# Main.net
KiCad netlist of a schematic drawn in Altium Designer
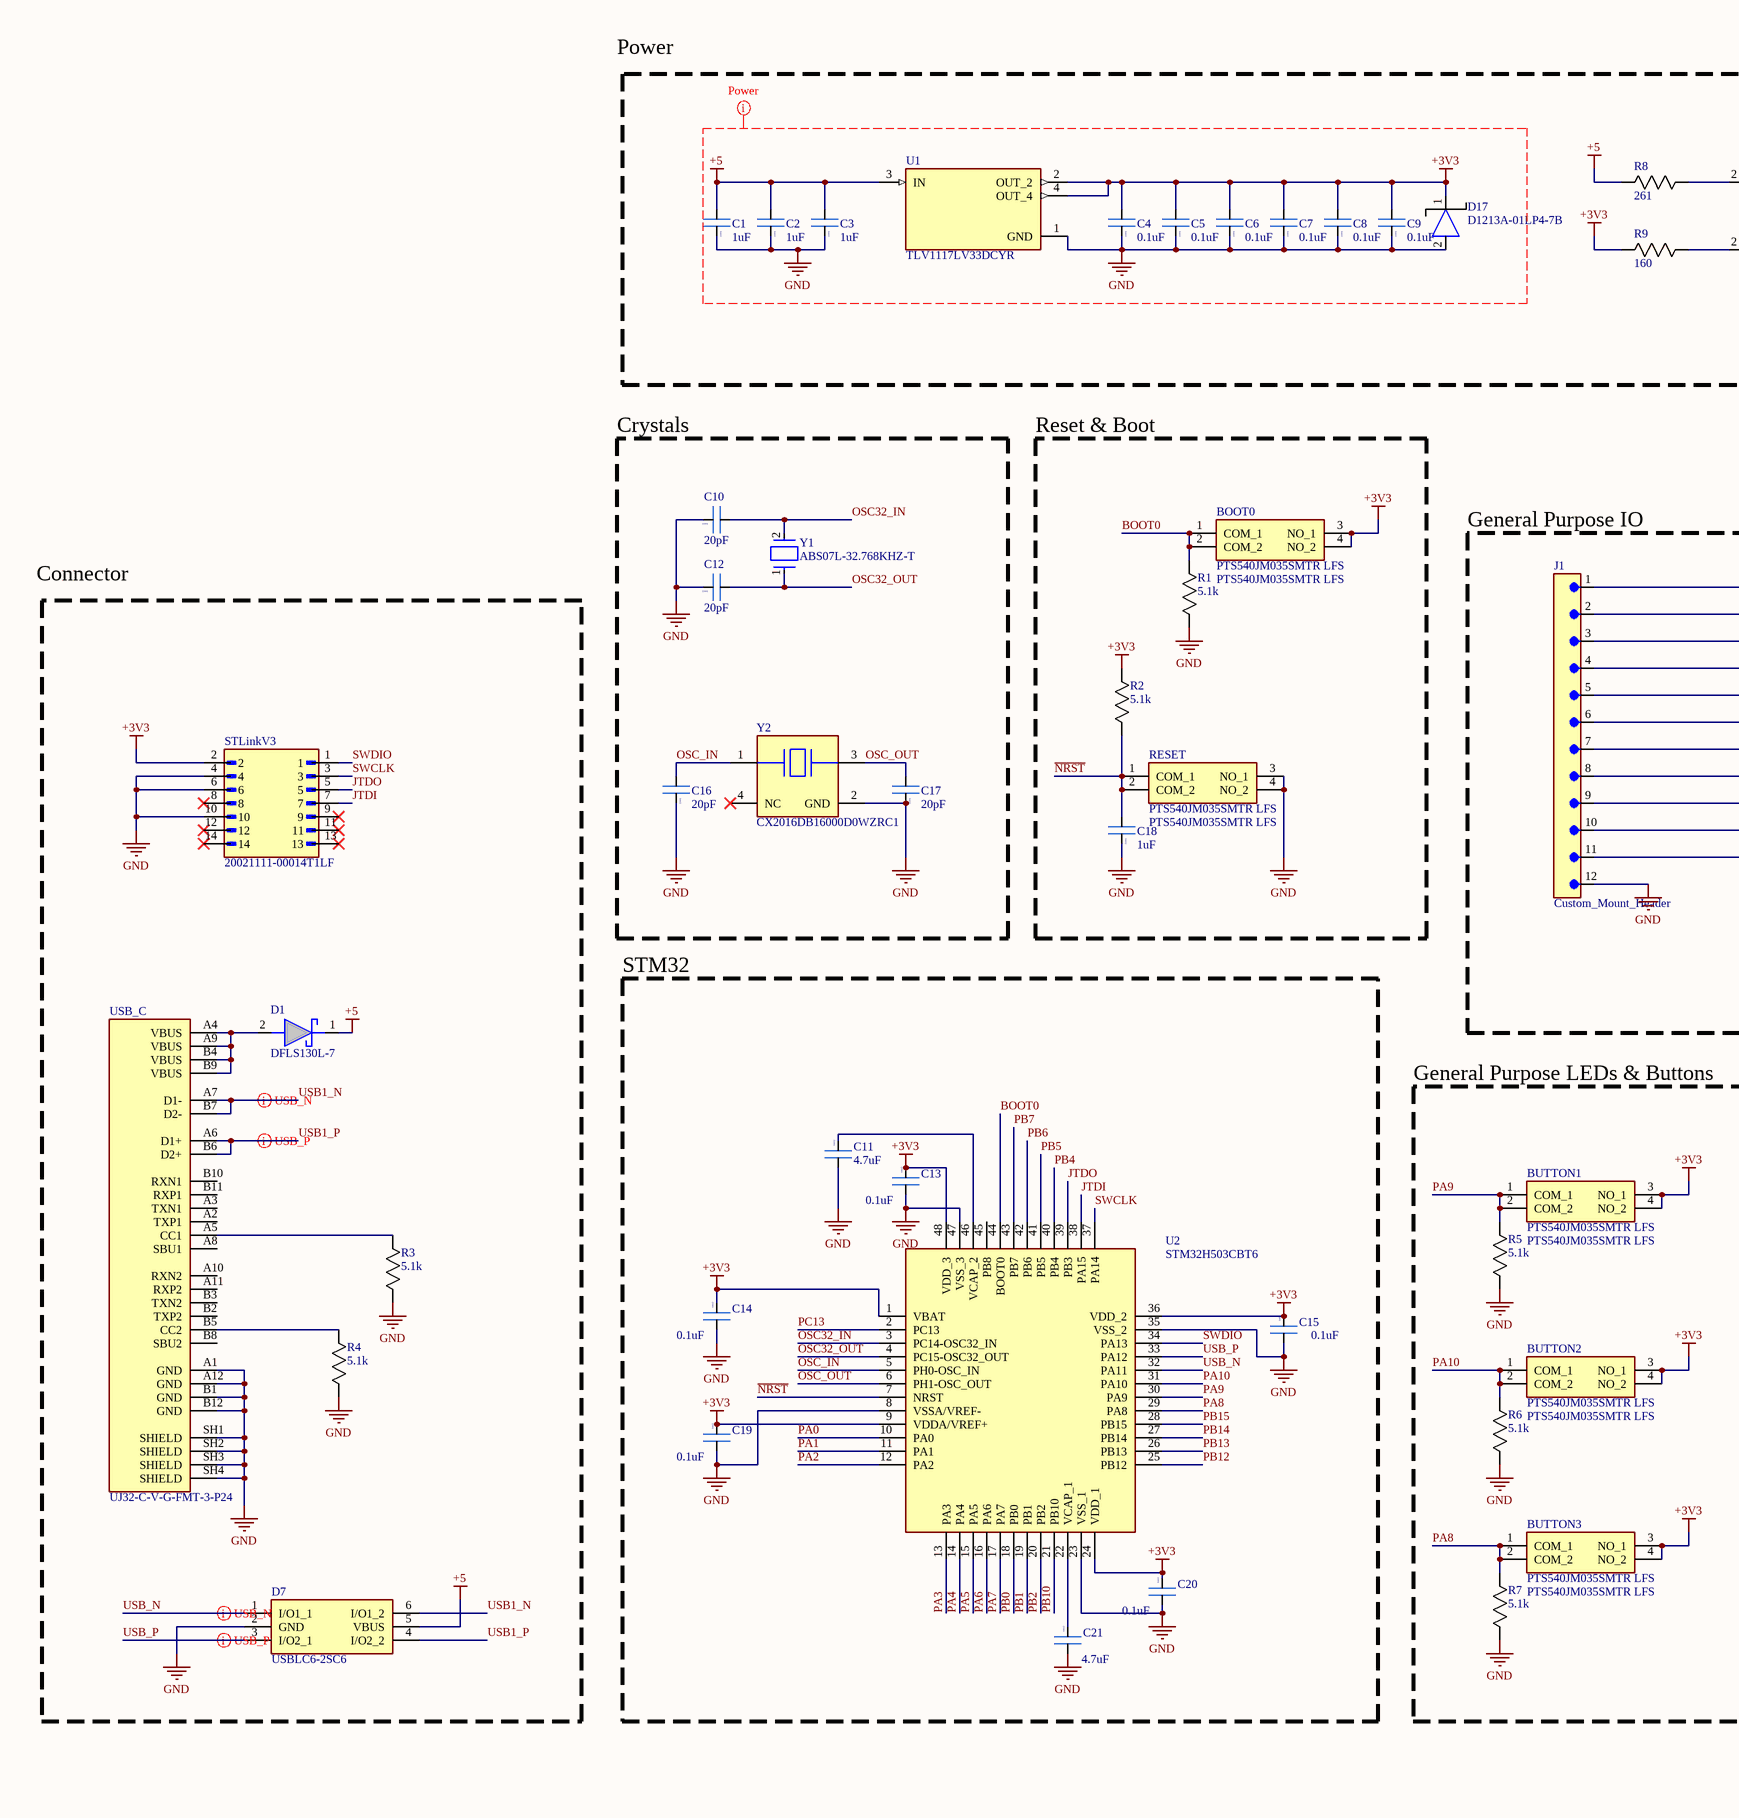
[diagram p0: Main.SchDoc, left]
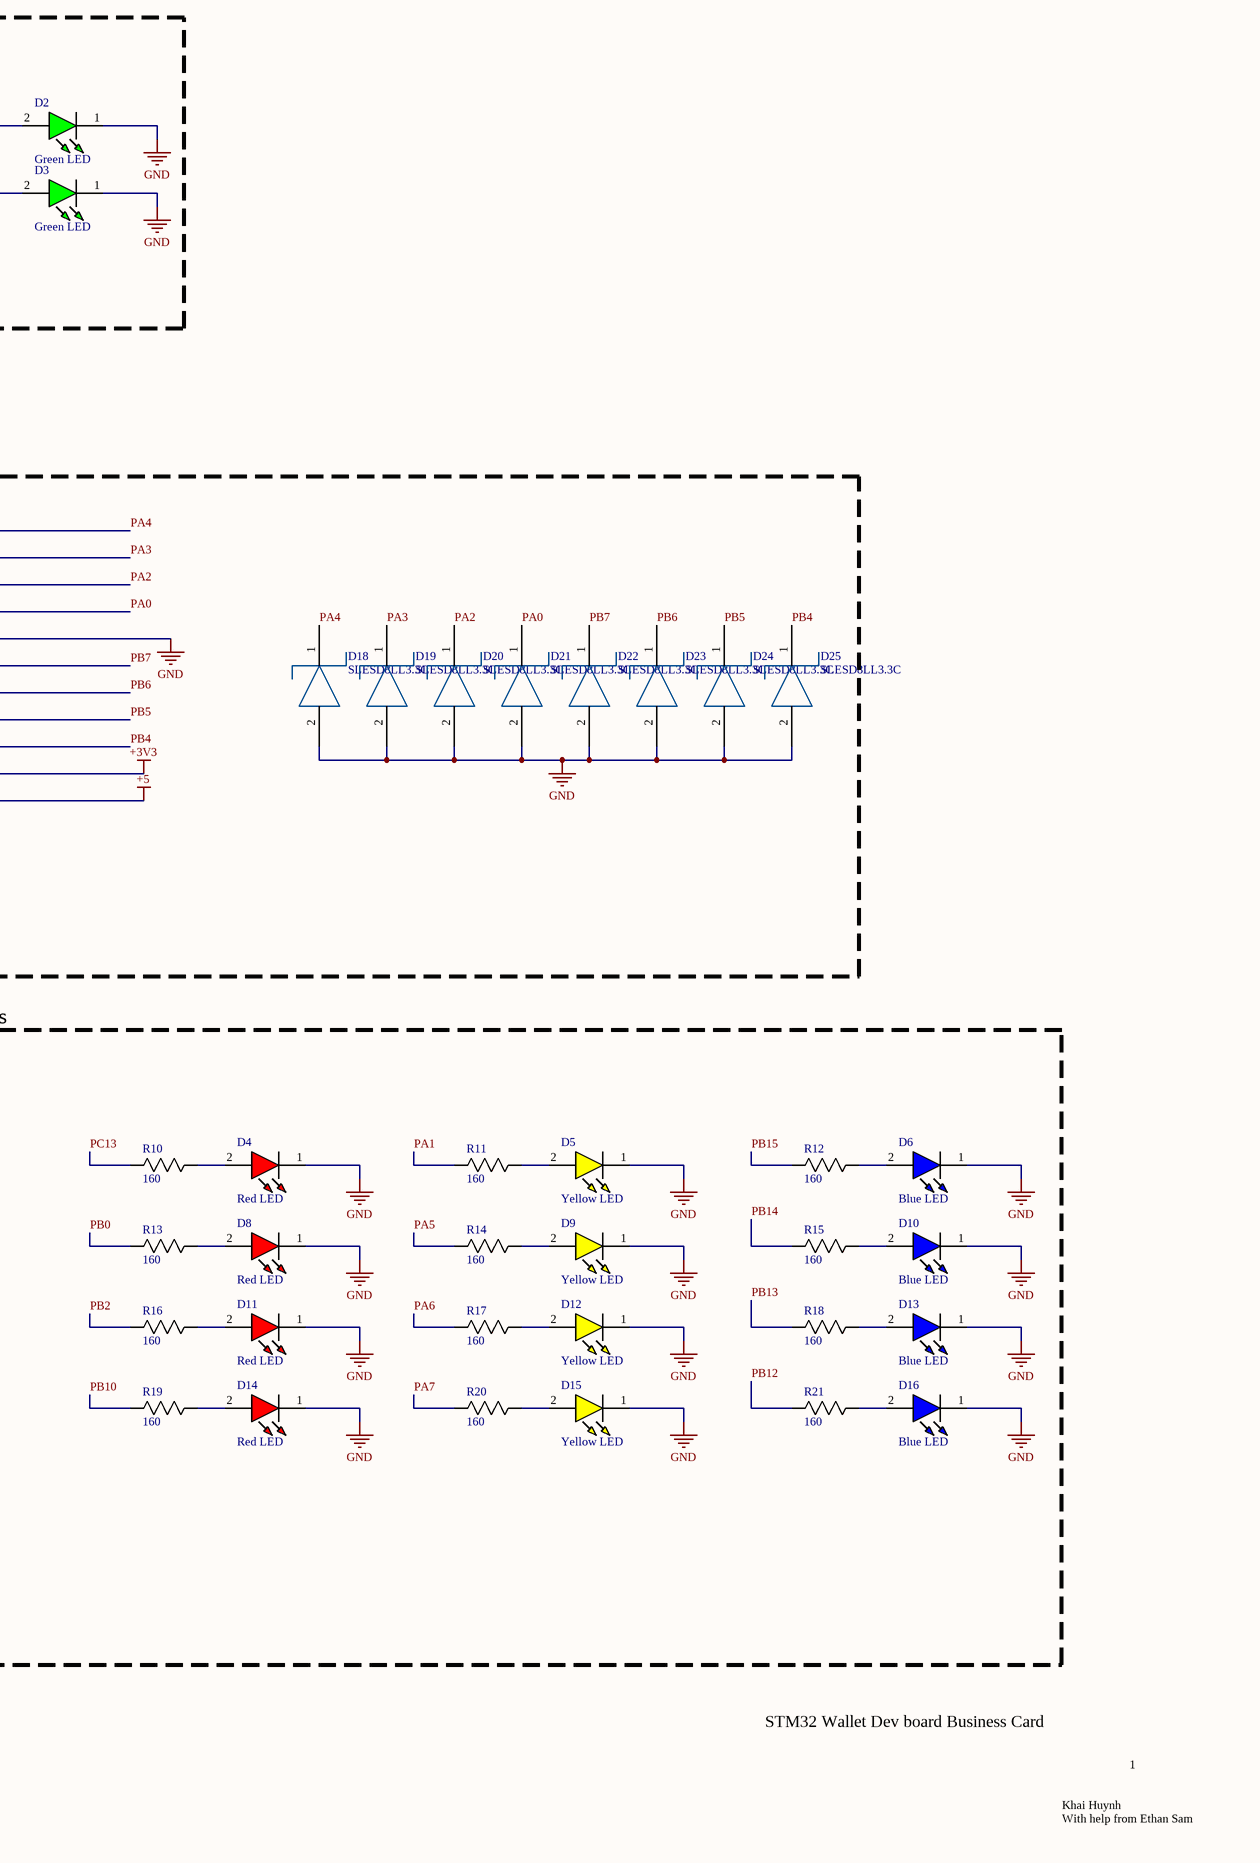
[diagram p1: Main.SchDoc, right]

(export (version "E")
  (design (tool "Eeschema 10.0.6"))
  (components
    (comp (ref "BOOT0")
      (value "PTS540JM035SMTR LFS")
      (footprint "PTS540JM035SMTR LFS")
      (libsource (lib "Schlib1") (part "PTS540JM035SMTR LFS"))
    )
    (comp (ref "BUTTON1")
      (value "PTS540JM035SMTR LFS")
      (footprint "PTS540JM035SMTR LFS")
      (libsource (lib "Schlib1") (part "PTS540JM035SMTR LFS"))
    )
    (comp (ref "BUTTON2")
      (value "PTS540JM035SMTR LFS")
      (footprint "PTS540JM035SMTR LFS")
      (libsource (lib "Schlib1") (part "PTS540JM035SMTR LFS"))
    )
    (comp (ref "BUTTON3")
      (value "PTS540JM035SMTR LFS")
      (footprint "PTS540JM035SMTR LFS")
      (libsource (lib "Schlib1") (part "PTS540JM035SMTR LFS"))
    )
    (comp (ref "C1")
      (value "1uF")
      (footprint "0402 Capacitor")
      (libsource (lib "Schlib1") (part "0402 Capacitor"))
    )
    (comp (ref "C2")
      (value "1uF")
      (footprint "0402 Capacitor")
      (libsource (lib "Schlib1") (part "0402 Capacitor"))
    )
    (comp (ref "C3")
      (value "1uF")
      (footprint "0402 Capacitor")
      (libsource (lib "Schlib1") (part "0402 Capacitor"))
    )
    (comp (ref "C4")
      (value "0.1uF")
      (footprint "0402 Capacitor")
      (libsource (lib "Schlib1") (part "0402 Capacitor"))
    )
    (comp (ref "C5")
      (value "0.1uF")
      (footprint "0402 Capacitor")
      (libsource (lib "Schlib1") (part "0402 Capacitor"))
    )
    (comp (ref "C6")
      (value "0.1uF")
      (footprint "0402 Capacitor")
      (libsource (lib "Schlib1") (part "0402 Capacitor"))
    )
    (comp (ref "C7")
      (value "0.1uF")
      (footprint "0402 Capacitor")
      (libsource (lib "Schlib1") (part "0402 Capacitor"))
    )
    (comp (ref "C8")
      (value "0.1uF")
      (footprint "0402 Capacitor")
      (libsource (lib "Schlib1") (part "0402 Capacitor"))
    )
    (comp (ref "C9")
      (value "0.1uF")
      (footprint "0402 Capacitor")
      (libsource (lib "Schlib1") (part "0402 Capacitor"))
    )
    (comp (ref "C10")
      (value "20pF")
      (footprint "0402 Capacitor")
      (libsource (lib "Schlib1") (part "0402 Capacitor"))
    )
    (comp (ref "C11")
      (value "4.7uF")
      (footprint "0402 Capacitor")
      (libsource (lib "Schlib1") (part "0402 Capacitor"))
    )
    (comp (ref "C12")
      (value "20pF")
      (footprint "0402 Capacitor")
      (libsource (lib "Schlib1") (part "0402 Capacitor"))
    )
    (comp (ref "C13")
      (value "0.1uF")
      (footprint "0402 Capacitor")
      (libsource (lib "Schlib1") (part "0402 Capacitor"))
    )
    (comp (ref "C14")
      (value "0.1uF")
      (footprint "0402 Capacitor")
      (libsource (lib "Schlib1") (part "0402 Capacitor"))
    )
    (comp (ref "C15")
      (value "0.1uF")
      (footprint "0402 Capacitor")
      (libsource (lib "Schlib1") (part "0402 Capacitor"))
    )
    (comp (ref "C16")
      (value "20pF")
      (footprint "0402 Capacitor")
      (libsource (lib "Schlib1") (part "0402 Capacitor"))
    )
    (comp (ref "C17")
      (value "20pF")
      (footprint "0402 Capacitor")
      (libsource (lib "Schlib1") (part "0402 Capacitor"))
    )
    (comp (ref "C18")
      (value "1uF")
      (footprint "0402 Capacitor")
      (libsource (lib "Schlib1") (part "0402 Capacitor"))
    )
    (comp (ref "C19")
      (value "0.1uF")
      (footprint "0402 Capacitor")
      (libsource (lib "Schlib1") (part "0402 Capacitor"))
    )
    (comp (ref "C20")
      (value "0.1uF")
      (footprint "0402 Capacitor")
      (libsource (lib "Schlib1") (part "0402 Capacitor"))
    )
    (comp (ref "C21")
      (value "4.7uF")
      (footprint "0402 Capacitor")
      (libsource (lib "Schlib1") (part "0402 Capacitor"))
    )
    (comp (ref "D1")
      (value "DFLS130L-7")
      (footprint "PCBComponent_1")
      (libsource (lib "Schlib1") (part "DFLS130L-7"))
    )
    (comp (ref "D2")
      (value "Green LED")
      (footprint "0603 LED")
      (description "APG1608CGKC/T")
      (libsource (lib "Schlib1") (part "Green LED"))
    )
    (comp (ref "D3")
      (value "Green LED")
      (footprint "0603 LED")
      (description "APG1608CGKC/T")
      (libsource (lib "Schlib1") (part "Green LED"))
    )
    (comp (ref "D4")
      (value "Red LED")
      (footprint "0603 LED")
      (description "APG1608SURKC/T")
      (libsource (lib "Schlib1") (part "Red LED"))
    )
    (comp (ref "D5")
      (value "Yellow LED")
      (footprint "0603 LED")
      (description "APG1608SYKC/T")
      (libsource (lib "Schlib1") (part "White LED"))
    )
    (comp (ref "D6")
      (value "Blue LED")
      (footprint "0603 LED")
      (description "APG1608QBC/D")
      (libsource (lib "Schlib1") (part "Blue LED"))
    )
    (comp (ref "D7")
      (value "USBLC6-2SC6")
      (footprint "USBLC6-2SC6")
      (libsource (lib "Schlib1") (part "USBLC6-2SC6"))
    )
    (comp (ref "D8")
      (value "Red LED")
      (footprint "0603 LED")
      (description "APG1608SURKC/T")
      (libsource (lib "Schlib1") (part "Red LED"))
    )
    (comp (ref "D9")
      (value "Yellow LED")
      (footprint "0603 LED")
      (description "APG1608SYKC/T")
      (libsource (lib "Schlib1") (part "White LED"))
    )
    (comp (ref "D10")
      (value "Blue LED")
      (footprint "0603 LED")
      (description "APG1608QBC/D")
      (libsource (lib "Schlib1") (part "Blue LED"))
    )
    (comp (ref "D11")
      (value "Red LED")
      (footprint "0603 LED")
      (description "APG1608SURKC/T")
      (libsource (lib "Schlib1") (part "Red LED"))
    )
    (comp (ref "D12")
      (value "Yellow LED")
      (footprint "0603 LED")
      (description "APG1608SYKC/T")
      (libsource (lib "Schlib1") (part "White LED"))
    )
    (comp (ref "D13")
      (value "Blue LED")
      (footprint "0603 LED")
      (description "APG1608QBC/D")
      (libsource (lib "Schlib1") (part "Blue LED"))
    )
    (comp (ref "D14")
      (value "Red LED")
      (footprint "0603 LED")
      (description "APG1608SURKC/T")
      (libsource (lib "Schlib1") (part "Red LED"))
    )
    (comp (ref "D15")
      (value "Yellow LED")
      (footprint "0603 LED")
      (description "APG1608SYKC/T")
      (libsource (lib "Schlib1") (part "White LED"))
    )
    (comp (ref "D16")
      (value "Blue LED")
      (footprint "0603 LED")
      (description "APG1608QBC/D")
      (libsource (lib "Schlib1") (part "Blue LED"))
    )
    (comp (ref "D17")
      (value "D1213A-01LP4-7B")
      (footprint "SLESD8LL3.3C")
      (libsource (lib "Schlib1") (part "D1213A-01LP4-7B"))
    )
    (comp (ref "D18")
      (value "SLESD8LL3.3C")
      (footprint "SLESD8LL3.3C")
      (libsource (lib "Schlib1") (part "SLESD8LL3.3C"))
    )
    (comp (ref "D19")
      (value "SLESD8LL3.3C")
      (footprint "SLESD8LL3.3C")
      (libsource (lib "Schlib1") (part "SLESD8LL3.3C"))
    )
    (comp (ref "D20")
      (value "SLESD8LL3.3C")
      (footprint "SLESD8LL3.3C")
      (libsource (lib "Schlib1") (part "SLESD8LL3.3C"))
    )
    (comp (ref "D21")
      (value "SLESD8LL3.3C")
      (footprint "SLESD8LL3.3C")
      (libsource (lib "Schlib1") (part "SLESD8LL3.3C"))
    )
    (comp (ref "D22")
      (value "SLESD8LL3.3C")
      (footprint "SLESD8LL3.3C")
      (libsource (lib "Schlib1") (part "SLESD8LL3.3C"))
    )
    (comp (ref "D23")
      (value "SLESD8LL3.3C")
      (footprint "SLESD8LL3.3C")
      (libsource (lib "Schlib1") (part "SLESD8LL3.3C"))
    )
    (comp (ref "D24")
      (value "SLESD8LL3.3C")
      (footprint "SLESD8LL3.3C")
      (libsource (lib "Schlib1") (part "SLESD8LL3.3C"))
    )
    (comp (ref "D25")
      (value "SLESD8LL3.3C")
      (footprint "SLESD8LL3.3C")
      (libsource (lib "Schlib1") (part "SLESD8LL3.3C"))
    )
    (comp (ref "J1")
      (value "Custom_Mount_Header")
      (footprint "Custom_header")
      (libsource (lib "Schlib1") (part "Custom_Mount_Header"))
    )
    (comp (ref "R1")
      (value "5.1k")
      (footprint "0402 Resistor")
      (libsource (lib "Schlib1") (part "0402 Resistor"))
    )
    (comp (ref "R2")
      (value "5.1k")
      (footprint "0402 Resistor")
      (libsource (lib "Schlib1") (part "0402 Resistor"))
    )
    (comp (ref "R3")
      (value "5.1k")
      (footprint "0402 Resistor")
      (libsource (lib "Schlib1") (part "0402 Resistor"))
    )
    (comp (ref "R4")
      (value "5.1k")
      (footprint "0402 Resistor")
      (libsource (lib "Schlib1") (part "0402 Resistor"))
    )
    (comp (ref "R5")
      (value "5.1k")
      (footprint "0402 Resistor")
      (libsource (lib "Schlib1") (part "0402 Resistor"))
    )
    (comp (ref "R6")
      (value "5.1k")
      (footprint "0402 Resistor")
      (libsource (lib "Schlib1") (part "0402 Resistor"))
    )
    (comp (ref "R7")
      (value "5.1k")
      (footprint "0402 Resistor")
      (libsource (lib "Schlib1") (part "0402 Resistor"))
    )
    (comp (ref "R8")
      (value "261")
      (footprint "0402 Resistor")
      (libsource (lib "Schlib1") (part "0402 Resistor"))
    )
    (comp (ref "R9")
      (value "160")
      (footprint "0402 Resistor")
      (libsource (lib "Schlib1") (part "0402 Resistor"))
    )
    (comp (ref "R10")
      (value "160")
      (footprint "0402 Resistor")
      (libsource (lib "Schlib1") (part "0402 Resistor"))
    )
    (comp (ref "R11")
      (value "160")
      (footprint "0402 Resistor")
      (libsource (lib "Schlib1") (part "0402 Resistor"))
    )
    (comp (ref "R12")
      (value "160")
      (footprint "0402 Resistor")
      (libsource (lib "Schlib1") (part "0402 Resistor"))
    )
    (comp (ref "R13")
      (value "160")
      (footprint "0402 Resistor")
      (libsource (lib "Schlib1") (part "0402 Resistor"))
    )
    (comp (ref "R14")
      (value "160")
      (footprint "0402 Resistor")
      (libsource (lib "Schlib1") (part "0402 Resistor"))
    )
    (comp (ref "R15")
      (value "160")
      (footprint "0402 Resistor")
      (libsource (lib "Schlib1") (part "0402 Resistor"))
    )
    (comp (ref "R16")
      (value "160")
      (footprint "0402 Resistor")
      (libsource (lib "Schlib1") (part "0402 Resistor"))
    )
    (comp (ref "R17")
      (value "160")
      (footprint "0402 Resistor")
      (libsource (lib "Schlib1") (part "0402 Resistor"))
    )
    (comp (ref "R18")
      (value "160")
      (footprint "0402 Resistor")
      (libsource (lib "Schlib1") (part "0402 Resistor"))
    )
    (comp (ref "R19")
      (value "160")
      (footprint "0402 Resistor")
      (libsource (lib "Schlib1") (part "0402 Resistor"))
    )
    (comp (ref "R20")
      (value "160")
      (footprint "0402 Resistor")
      (libsource (lib "Schlib1") (part "0402 Resistor"))
    )
    (comp (ref "R21")
      (value "160")
      (footprint "0402 Resistor")
      (libsource (lib "Schlib1") (part "0402 Resistor"))
    )
    (comp (ref "RESET")
      (value "PTS540JM035SMTR LFS")
      (footprint "PTS540JM035SMTR LFS")
      (libsource (lib "Schlib1") (part "PTS540JM035SMTR LFS"))
    )
    (comp (ref "STLinkV3")
      (value "20021111-00014T1LF")
      (footprint "20021111-00014T1LF")
      (libsource (lib "Schlib1") (part "20021111-00014T1LF"))
    )
    (comp (ref "U1")
      (value "TLV1117LV33DCYR")
      (footprint "TLV1117LV33DCYR")
      (libsource (lib "Schlib1") (part "TLV1117LV33DCYR"))
    )
    (comp (ref "U2")
      (value "STM32H503CBT6")
      (footprint "STM32H503")
      (libsource (lib "Schlib1") (part "STM32H503CBT6"))
    )
    (comp (ref "USB_C")
      (value "UJ32-C-V-G-FMT-3-P24")
      (footprint "UJ32-C-V-G-FMT-3-P24")
      (libsource (lib "Schlib1") (part "UJ32-C-V-G-FMT-3-P24"))
    )
    (comp (ref "Y1")
      (value "ABS07L-32.768KHZ-T")
      (footprint "FP-ABS07L-MFG")
      (description "CRYSTAL 32.7680KHZ 12.5PF SMD")
      (fields (field (name "TOLERANCE") "20ppm"))
      (libsource (lib "Altium Content Vault") (part "c23a69dc6c9e2f18f2079038eb95dd1"))
    )
    (comp (ref "Y2")
      (value "CX2016DB16000D0WZRC1")
      (footprint "CX2016DB16000D0WZRC1")
      (libsource (lib "Schlib1") (part "CX2016DB16000D0WZRC1"))
    )
  )
  (nets
    (net (code "1") (name "+3V3") (class "Default")
      (node (ref "BOOT0") (pin "3") (pinfunction "NO_1_3") (pintype "passive"))
      (node (ref "BOOT0") (pin "4") (pinfunction "NO_2_4") (pintype "passive"))
      (node (ref "BUTTON1") (pin "3") (pinfunction "NO_1_3") (pintype "passive"))
      (node (ref "BUTTON1") (pin "4") (pinfunction "NO_2_4") (pintype "passive"))
      (node (ref "BUTTON2") (pin "3") (pinfunction "NO_1_3") (pintype "passive"))
      (node (ref "BUTTON2") (pin "4") (pinfunction "NO_2_4") (pintype "passive"))
      (node (ref "BUTTON3") (pin "3") (pinfunction "NO_1_3") (pintype "passive"))
      (node (ref "BUTTON3") (pin "4") (pinfunction "NO_2_4") (pintype "passive"))
      (node (ref "C13") (pin "1") (pinfunction "1_1") (pintype "passive"))
      (node (ref "C14") (pin "1") (pinfunction "1_1") (pintype "passive"))
      (node (ref "C15") (pin "1") (pinfunction "1_1") (pintype "passive"))
      (node (ref "C19") (pin "1") (pinfunction "1_1") (pintype "passive"))
      (node (ref "C20") (pin "1") (pinfunction "1_1") (pintype "passive"))
      (node (ref "C4") (pin "2") (pinfunction "2_2") (pintype "passive"))
      (node (ref "C5") (pin "2") (pinfunction "2_2") (pintype "passive"))
      (node (ref "C6") (pin "2") (pinfunction "2_2") (pintype "passive"))
      (node (ref "C7") (pin "2") (pinfunction "2_2") (pintype "passive"))
      (node (ref "C8") (pin "2") (pinfunction "2_2") (pintype "passive"))
      (node (ref "C9") (pin "2") (pinfunction "2_2") (pintype "passive"))
      (node (ref "D17") (pin "1") (pinfunction "1_1") (pintype "passive"))
      (node (ref "J1") (pin "10") (pinfunction "10_10") (pintype "passive"))
      (node (ref "R2") (pin "1") (pinfunction "1_1") (pintype "passive"))
      (node (ref "R9") (pin "1") (pinfunction "1_1") (pintype "passive"))
      (node (ref "STLinkV3") (pin "2") (pinfunction "2_2") (pintype "passive"))
      (node (ref "U1") (pin "2") (pinfunction "OUT_2_2") (pintype "output"))
      (node (ref "U1") (pin "4") (pinfunction "OUT_4_4") (pintype "output"))
      (node (ref "U2") (pin "1") (pinfunction "VBAT_1") (pintype "passive"))
      (node (ref "U2") (pin "24") (pinfunction "VDD_1_24") (pintype "passive"))
      (node (ref "U2") (pin "36") (pinfunction "VDD_2_36") (pintype "passive"))
      (node (ref "U2") (pin "48") (pinfunction "VDD_3_48") (pintype "passive"))
      (node (ref "U2") (pin "9") (pinfunction "VDDA/VREF+_9") (pintype "passive"))
    )
    (net (code "2") (name "+5") (class "Default")
      (node (ref "C1") (pin "2") (pinfunction "2_2") (pintype "passive"))
      (node (ref "C2") (pin "2") (pinfunction "2_2") (pintype "passive"))
      (node (ref "C3") (pin "2") (pinfunction "2_2") (pintype "passive"))
      (node (ref "D1") (pin "1") (pinfunction "K_1") (pintype "passive"))
      (node (ref "D7") (pin "5") (pinfunction "VBUS_5") (pintype "passive"))
      (node (ref "J1") (pin "11") (pinfunction "11_11") (pintype "passive"))
      (node (ref "R8") (pin "1") (pinfunction "1_1") (pintype "passive"))
      (node (ref "U1") (pin "3") (pinfunction "IN_3") (pintype "input"))
    )
    (net (code "3") (name "/BOOT0") (class "Default")
      (node (ref "BOOT0") (pin "1") (pinfunction "COM_1_1") (pintype "passive"))
      (node (ref "BOOT0") (pin "2") (pinfunction "COM_2_2") (pintype "passive"))
      (node (ref "R1") (pin "1") (pinfunction "1_1") (pintype "passive"))
      (node (ref "U2") (pin "44") (pinfunction "BOOT0_44") (pintype "passive"))
    )
    (net (code "4") (name "/JTDI") (class "Default")
      (node (ref "STLinkV3") (pin "7") (pinfunction "7_7") (pintype "passive"))
      (node (ref "U2") (pin "38") (pinfunction "PA15_38") (pintype "passive"))
    )
    (net (code "5") (name "/JTDO") (class "Default")
      (node (ref "STLinkV3") (pin "5") (pinfunction "5_5") (pintype "passive"))
      (node (ref "U2") (pin "39") (pinfunction "PB3_39") (pintype "passive"))
    )
    (net (code "6") (name "/OSC32_IN") (class "Default")
      (node (ref "C10") (pin "2") (pinfunction "2_2") (pintype "passive"))
      (node (ref "U2") (pin "3") (pinfunction "PC14-OSC32_IN_3") (pintype "passive"))
      (node (ref "Y1") (pin "2") (pinfunction "2_2") (pintype "passive"))
    )
    (net (code "7") (name "/OSC32_OUT") (class "Default")
      (node (ref "C12") (pin "2") (pinfunction "2_2") (pintype "passive"))
      (node (ref "U2") (pin "4") (pinfunction "PC15-OSC32_OUT_4") (pintype "passive"))
      (node (ref "Y1") (pin "1") (pinfunction "1_1") (pintype "passive"))
    )
    (net (code "8") (name "/OSC_IN") (class "Default")
      (node (ref "C16") (pin "2") (pinfunction "2_2") (pintype "passive"))
      (node (ref "U2") (pin "5") (pinfunction "PH0-OSC_IN_5") (pintype "passive"))
      (node (ref "Y2") (pin "1") (pinfunction "1_1") (pintype "passive"))
    )
    (net (code "9") (name "/OSC_OUT") (class "Default")
      (node (ref "C17") (pin "2") (pinfunction "2_2") (pintype "passive"))
      (node (ref "U2") (pin "6") (pinfunction "PH1-OSC_OUT_6") (pintype "passive"))
      (node (ref "Y2") (pin "3") (pinfunction "3_3") (pintype "passive"))
    )
    (net (code "10") (name "/PA0") (class "Default")
      (node (ref "D21") (pin "1") (pinfunction "1_1") (pintype "passive"))
      (node (ref "J1") (pin "4") (pinfunction "4_4") (pintype "passive"))
      (node (ref "U2") (pin "10") (pinfunction "PA0_10") (pintype "passive"))
    )
    (net (code "11") (name "/PA1") (class "Default")
      (node (ref "R11") (pin "1") (pinfunction "1_1") (pintype "passive"))
      (node (ref "U2") (pin "11") (pinfunction "PA1_11") (pintype "passive"))
    )
    (net (code "12") (name "/PA2") (class "Default")
      (node (ref "D20") (pin "1") (pinfunction "1_1") (pintype "passive"))
      (node (ref "J1") (pin "3") (pinfunction "3_3") (pintype "passive"))
      (node (ref "U2") (pin "12") (pinfunction "PA2_12") (pintype "passive"))
    )
    (net (code "13") (name "/PA3") (class "Default")
      (node (ref "D19") (pin "1") (pinfunction "1_1") (pintype "passive"))
      (node (ref "J1") (pin "2") (pinfunction "2_2") (pintype "passive"))
      (node (ref "U2") (pin "13") (pinfunction "PA3_13") (pintype "passive"))
    )
    (net (code "14") (name "/PA4") (class "Default")
      (node (ref "D18") (pin "1") (pinfunction "1_1") (pintype "passive"))
      (node (ref "J1") (pin "1") (pinfunction "1_1") (pintype "passive"))
      (node (ref "U2") (pin "14") (pinfunction "PA4_14") (pintype "passive"))
    )
    (net (code "15") (name "/PA5") (class "Default")
      (node (ref "R14") (pin "1") (pinfunction "1_1") (pintype "passive"))
      (node (ref "U2") (pin "15") (pinfunction "PA5_15") (pintype "passive"))
    )
    (net (code "16") (name "/PA6") (class "Default")
      (node (ref "R17") (pin "1") (pinfunction "1_1") (pintype "passive"))
      (node (ref "U2") (pin "16") (pinfunction "PA6_16") (pintype "passive"))
    )
    (net (code "17") (name "/PA7") (class "Default")
      (node (ref "R20") (pin "1") (pinfunction "1_1") (pintype "passive"))
      (node (ref "U2") (pin "17") (pinfunction "PA7_17") (pintype "passive"))
    )
    (net (code "18") (name "/PA8") (class "Default")
      (node (ref "BUTTON3") (pin "1") (pinfunction "COM_1_1") (pintype "passive"))
      (node (ref "BUTTON3") (pin "2") (pinfunction "COM_2_2") (pintype "passive"))
      (node (ref "R7") (pin "1") (pinfunction "1_1") (pintype "passive"))
      (node (ref "U2") (pin "29") (pinfunction "PA8_29") (pintype "passive"))
    )
    (net (code "19") (name "/PA9") (class "Default")
      (node (ref "BUTTON1") (pin "1") (pinfunction "COM_1_1") (pintype "passive"))
      (node (ref "BUTTON1") (pin "2") (pinfunction "COM_2_2") (pintype "passive"))
      (node (ref "R5") (pin "1") (pinfunction "1_1") (pintype "passive"))
      (node (ref "U2") (pin "30") (pinfunction "PA9_30") (pintype "passive"))
    )
    (net (code "20") (name "/PA10") (class "Default")
      (node (ref "BUTTON2") (pin "1") (pinfunction "COM_1_1") (pintype "passive"))
      (node (ref "BUTTON2") (pin "2") (pinfunction "COM_2_2") (pintype "passive"))
      (node (ref "R6") (pin "1") (pinfunction "1_1") (pintype "passive"))
      (node (ref "U2") (pin "31") (pinfunction "PA10_31") (pintype "passive"))
    )
    (net (code "21") (name "/PB0") (class "Default")
      (node (ref "R13") (pin "1") (pinfunction "1_1") (pintype "passive"))
      (node (ref "U2") (pin "18") (pinfunction "PB0_18") (pintype "passive"))
    )
    (net (code "22") (name "/PB1") (class "Default")
      (node (ref "U2") (pin "19") (pinfunction "PB1_19") (pintype "passive"))
    )
    (net (code "23") (name "/PB2") (class "Default")
      (node (ref "R16") (pin "1") (pinfunction "1_1") (pintype "passive"))
      (node (ref "U2") (pin "20") (pinfunction "PB2_20") (pintype "passive"))
    )
    (net (code "24") (name "/PB4") (class "Default")
      (node (ref "D25") (pin "1") (pinfunction "1_1") (pintype "passive"))
      (node (ref "J1") (pin "9") (pinfunction "9_9") (pintype "passive"))
      (node (ref "U2") (pin "40") (pinfunction "PB4_40") (pintype "passive"))
    )
    (net (code "25") (name "/PB5") (class "Default")
      (node (ref "D24") (pin "1") (pinfunction "1_1") (pintype "passive"))
      (node (ref "J1") (pin "8") (pinfunction "8_8") (pintype "passive"))
      (node (ref "U2") (pin "41") (pinfunction "PB5_41") (pintype "passive"))
    )
    (net (code "26") (name "/PB6") (class "Default")
      (node (ref "D23") (pin "1") (pinfunction "1_1") (pintype "passive"))
      (node (ref "J1") (pin "7") (pinfunction "7_7") (pintype "passive"))
      (node (ref "U2") (pin "42") (pinfunction "PB6_42") (pintype "passive"))
    )
    (net (code "27") (name "/PB7") (class "Default")
      (node (ref "D22") (pin "1") (pinfunction "1_1") (pintype "passive"))
      (node (ref "J1") (pin "6") (pinfunction "6_6") (pintype "passive"))
      (node (ref "U2") (pin "43") (pinfunction "PB7_43") (pintype "passive"))
    )
    (net (code "28") (name "/PB10") (class "Default")
      (node (ref "R19") (pin "1") (pinfunction "1_1") (pintype "passive"))
      (node (ref "U2") (pin "21") (pinfunction "PB10_21") (pintype "passive"))
    )
    (net (code "29") (name "/PB12") (class "Default")
      (node (ref "R21") (pin "1") (pinfunction "1_1") (pintype "passive"))
      (node (ref "U2") (pin "25") (pinfunction "PB12_25") (pintype "passive"))
    )
    (net (code "30") (name "/PB13") (class "Default")
      (node (ref "R18") (pin "1") (pinfunction "1_1") (pintype "passive"))
      (node (ref "U2") (pin "26") (pinfunction "PB13_26") (pintype "passive"))
    )
    (net (code "31") (name "/PB14") (class "Default")
      (node (ref "R15") (pin "1") (pinfunction "1_1") (pintype "passive"))
      (node (ref "U2") (pin "27") (pinfunction "PB14_27") (pintype "passive"))
    )
    (net (code "32") (name "/PB15") (class "Default")
      (node (ref "R12") (pin "1") (pinfunction "1_1") (pintype "passive"))
      (node (ref "U2") (pin "28") (pinfunction "PB15_28") (pintype "passive"))
    )
    (net (code "33") (name "/PC13") (class "Default")
      (node (ref "R10") (pin "1") (pinfunction "1_1") (pintype "passive"))
      (node (ref "U2") (pin "2") (pinfunction "PC13_2") (pintype "passive"))
    )
    (net (code "34") (name "/SWCLK") (class "Default")
      (node (ref "STLinkV3") (pin "3") (pinfunction "3_3") (pintype "passive"))
      (node (ref "U2") (pin "37") (pinfunction "PA14_37") (pintype "passive"))
    )
    (net (code "35") (name "/SWDIO") (class "Default")
      (node (ref "STLinkV3") (pin "1") (pinfunction "1_1") (pintype "passive"))
      (node (ref "U2") (pin "34") (pinfunction "PA13_34") (pintype "passive"))
    )
    (net (code "36") (name "/USB1_N") (class "Default")
      (node (ref "D7") (pin "6") (pinfunction "I/O1_2_6") (pintype "passive"))
      (node (ref "USB_C") (pin "A7") (pinfunction "D1-_A7") (pintype "passive"))
      (node (ref "USB_C") (pin "B7") (pinfunction "D2-_B7") (pintype "passive"))
    )
    (net (code "37") (name "/USB1_P") (class "Default")
      (node (ref "D7") (pin "4") (pinfunction "I/O2_2_4") (pintype "passive"))
      (node (ref "USB_C") (pin "A6") (pinfunction "D1+_A6") (pintype "passive"))
      (node (ref "USB_C") (pin "B6") (pinfunction "D2+_B6") (pintype "passive"))
    )
    (net (code "38") (name "/USB_N") (class "Default")
      (node (ref "D7") (pin "1") (pinfunction "I/O1_1_1") (pintype "passive"))
      (node (ref "U2") (pin "32") (pinfunction "PA11_32") (pintype "passive"))
    )
    (net (code "39") (name "/USB_P") (class "Default")
      (node (ref "D7") (pin "3") (pinfunction "I/O2_1_3") (pintype "passive"))
      (node (ref "U2") (pin "33") (pinfunction "PA12_33") (pintype "passive"))
    )
    (net (code "40") (name "/~{NRST}") (class "Default")
      (node (ref "C18") (pin "2") (pinfunction "2_2") (pintype "passive"))
      (node (ref "R2") (pin "2") (pinfunction "2_2") (pintype "passive"))
      (node (ref "RESET") (pin "1") (pinfunction "COM_1_1") (pintype "passive"))
      (node (ref "RESET") (pin "2") (pinfunction "COM_2_2") (pintype "passive"))
      (node (ref "U2") (pin "7") (pinfunction "NRST_7") (pintype "passive"))
    )
    (net (code "41") (name "GND") (class "Default")
      (node (ref "C1") (pin "1") (pinfunction "1_1") (pintype "passive"))
      (node (ref "C10") (pin "1") (pinfunction "1_1") (pintype "passive"))
      (node (ref "C11") (pin "2") (pinfunction "2_2") (pintype "passive"))
      (node (ref "C12") (pin "1") (pinfunction "1_1") (pintype "passive"))
      (node (ref "C13") (pin "2") (pinfunction "2_2") (pintype "passive"))
      (node (ref "C14") (pin "2") (pinfunction "2_2") (pintype "passive"))
      (node (ref "C15") (pin "2") (pinfunction "2_2") (pintype "passive"))
      (node (ref "C16") (pin "1") (pinfunction "1_1") (pintype "passive"))
      (node (ref "C17") (pin "1") (pinfunction "1_1") (pintype "passive"))
      (node (ref "C18") (pin "1") (pinfunction "1_1") (pintype "passive"))
      (node (ref "C19") (pin "2") (pinfunction "2_2") (pintype "passive"))
      (node (ref "C2") (pin "1") (pinfunction "1_1") (pintype "passive"))
      (node (ref "C20") (pin "2") (pinfunction "2_2") (pintype "passive"))
      (node (ref "C21") (pin "2") (pinfunction "2_2") (pintype "passive"))
      (node (ref "C3") (pin "1") (pinfunction "1_1") (pintype "passive"))
      (node (ref "C4") (pin "1") (pinfunction "1_1") (pintype "passive"))
      (node (ref "C5") (pin "1") (pinfunction "1_1") (pintype "passive"))
      (node (ref "C6") (pin "1") (pinfunction "1_1") (pintype "passive"))
      (node (ref "C7") (pin "1") (pinfunction "1_1") (pintype "passive"))
      (node (ref "C8") (pin "1") (pinfunction "1_1") (pintype "passive"))
      (node (ref "C9") (pin "1") (pinfunction "1_1") (pintype "passive"))
      (node (ref "D10") (pin "1") (pinfunction "K_1") (pintype "passive"))
      (node (ref "D11") (pin "1") (pinfunction "K_1") (pintype "passive"))
      (node (ref "D12") (pin "1") (pinfunction "K_1") (pintype "passive"))
      (node (ref "D13") (pin "1") (pinfunction "K_1") (pintype "passive"))
      (node (ref "D14") (pin "1") (pinfunction "K_1") (pintype "passive"))
      (node (ref "D15") (pin "1") (pinfunction "K_1") (pintype "passive"))
      (node (ref "D16") (pin "1") (pinfunction "K_1") (pintype "passive"))
      (node (ref "D17") (pin "2") (pinfunction "2_2") (pintype "passive"))
      (node (ref "D18") (pin "2") (pinfunction "2_2") (pintype "passive"))
      (node (ref "D19") (pin "2") (pinfunction "2_2") (pintype "passive"))
      (node (ref "D2") (pin "1") (pinfunction "K_1") (pintype "passive"))
      (node (ref "D20") (pin "2") (pinfunction "2_2") (pintype "passive"))
      (node (ref "D21") (pin "2") (pinfunction "2_2") (pintype "passive"))
      (node (ref "D22") (pin "2") (pinfunction "2_2") (pintype "passive"))
      (node (ref "D23") (pin "2") (pinfunction "2_2") (pintype "passive"))
      (node (ref "D24") (pin "2") (pinfunction "2_2") (pintype "passive"))
      (node (ref "D25") (pin "2") (pinfunction "2_2") (pintype "passive"))
      (node (ref "D3") (pin "1") (pinfunction "K_1") (pintype "passive"))
      (node (ref "D4") (pin "1") (pinfunction "K_1") (pintype "passive"))
      (node (ref "D5") (pin "1") (pinfunction "K_1") (pintype "passive"))
      (node (ref "D6") (pin "1") (pinfunction "K_1") (pintype "passive"))
      (node (ref "D7") (pin "2") (pinfunction "GND_2") (pintype "passive"))
      (node (ref "D8") (pin "1") (pinfunction "K_1") (pintype "passive"))
      (node (ref "D9") (pin "1") (pinfunction "K_1") (pintype "passive"))
      (node (ref "J1") (pin "12") (pinfunction "12_12") (pintype "passive"))
      (node (ref "J1") (pin "5") (pinfunction "5_5") (pintype "passive"))
      (node (ref "R1") (pin "2") (pinfunction "2_2") (pintype "passive"))
      (node (ref "R3") (pin "2") (pinfunction "2_2") (pintype "passive"))
      (node (ref "R4") (pin "2") (pinfunction "2_2") (pintype "passive"))
      (node (ref "R5") (pin "2") (pinfunction "2_2") (pintype "passive"))
      (node (ref "R6") (pin "2") (pinfunction "2_2") (pintype "passive"))
      (node (ref "R7") (pin "2") (pinfunction "2_2") (pintype "passive"))
      (node (ref "RESET") (pin "3") (pinfunction "NO_1_3") (pintype "passive"))
      (node (ref "RESET") (pin "4") (pinfunction "NO_2_4") (pintype "passive"))
      (node (ref "STLinkV3") (pin "10") (pinfunction "10_10") (pintype "passive"))
      (node (ref "STLinkV3") (pin "4") (pinfunction "4_4") (pintype "passive"))
      (node (ref "STLinkV3") (pin "6") (pinfunction "6_6") (pintype "passive"))
      (node (ref "U1") (pin "1") (pinfunction "GND_1") (pintype "power_in"))
      (node (ref "U2") (pin "23") (pinfunction "VSS_1_23") (pintype "passive"))
      (node (ref "U2") (pin "35") (pinfunction "VSS_2_35") (pintype "passive"))
      (node (ref "U2") (pin "47") (pinfunction "VSS_3_47") (pintype "passive"))
      (node (ref "U2") (pin "8") (pinfunction "VSSA/VREF-_8") (pintype "passive"))
      (node (ref "USB_C") (pin "A1") (pinfunction "GND_A1") (pintype "passive"))
      (node (ref "USB_C") (pin "A12") (pinfunction "GND_A12") (pintype "passive"))
      (node (ref "USB_C") (pin "B1") (pinfunction "GND_B1") (pintype "passive"))
      (node (ref "USB_C") (pin "B12") (pinfunction "GND_B12") (pintype "passive"))
      (node (ref "USB_C") (pin "SH1") (pinfunction "SHIELD_SH1") (pintype "passive"))
      (node (ref "USB_C") (pin "SH2") (pinfunction "SHIELD_SH2") (pintype "passive"))
      (node (ref "USB_C") (pin "SH3") (pinfunction "SHIELD_SH3") (pintype "passive"))
      (node (ref "USB_C") (pin "SH4") (pinfunction "SHIELD_SH4") (pintype "passive"))
      (node (ref "Y2") (pin "2") (pinfunction "GND_2") (pintype "power_in"))
    )
    (net (code "42") (name "Net-(D1-A)") (class "Default")
      (node (ref "D1") (pin "2") (pinfunction "A_2") (pintype "passive"))
      (node (ref "USB_C") (pin "A4") (pinfunction "VBUS_A4") (pintype "passive"))
      (node (ref "USB_C") (pin "A9") (pinfunction "VBUS_A9") (pintype "passive"))
      (node (ref "USB_C") (pin "B4") (pinfunction "VBUS_B4") (pintype "passive"))
      (node (ref "USB_C") (pin "B9") (pinfunction "VBUS_B9") (pintype "passive"))
    )
    (net (code "43") (name "Net-(D2-A)") (class "Default")
      (node (ref "D2") (pin "2") (pinfunction "A_2") (pintype "passive"))
      (node (ref "R8") (pin "2") (pinfunction "2_2") (pintype "passive"))
    )
    (net (code "44") (name "Net-(D3-A)") (class "Default")
      (node (ref "D3") (pin "2") (pinfunction "A_2") (pintype "passive"))
      (node (ref "R9") (pin "2") (pinfunction "2_2") (pintype "passive"))
    )
    (net (code "45") (name "Net-(D4-A)") (class "Default")
      (node (ref "D4") (pin "2") (pinfunction "A_2") (pintype "passive"))
      (node (ref "R10") (pin "2") (pinfunction "2_2") (pintype "passive"))
    )
    (net (code "46") (name "Net-(D5-A)") (class "Default")
      (node (ref "D5") (pin "2") (pinfunction "A_2") (pintype "passive"))
      (node (ref "R11") (pin "2") (pinfunction "2_2") (pintype "passive"))
    )
    (net (code "47") (name "Net-(D6-A)") (class "Default")
      (node (ref "D6") (pin "2") (pinfunction "A_2") (pintype "passive"))
      (node (ref "R12") (pin "2") (pinfunction "2_2") (pintype "passive"))
    )
    (net (code "48") (name "Net-(D8-A)") (class "Default")
      (node (ref "D8") (pin "2") (pinfunction "A_2") (pintype "passive"))
      (node (ref "R13") (pin "2") (pinfunction "2_2") (pintype "passive"))
    )
    (net (code "49") (name "Net-(D9-A)") (class "Default")
      (node (ref "D9") (pin "2") (pinfunction "A_2") (pintype "passive"))
      (node (ref "R14") (pin "2") (pinfunction "2_2") (pintype "passive"))
    )
    (net (code "50") (name "Net-(D10-A)") (class "Default")
      (node (ref "D10") (pin "2") (pinfunction "A_2") (pintype "passive"))
      (node (ref "R15") (pin "2") (pinfunction "2_2") (pintype "passive"))
    )
    (net (code "51") (name "Net-(D11-A)") (class "Default")
      (node (ref "D11") (pin "2") (pinfunction "A_2") (pintype "passive"))
      (node (ref "R16") (pin "2") (pinfunction "2_2") (pintype "passive"))
    )
    (net (code "52") (name "Net-(D12-A)") (class "Default")
      (node (ref "D12") (pin "2") (pinfunction "A_2") (pintype "passive"))
      (node (ref "R17") (pin "2") (pinfunction "2_2") (pintype "passive"))
    )
    (net (code "53") (name "Net-(D13-A)") (class "Default")
      (node (ref "D13") (pin "2") (pinfunction "A_2") (pintype "passive"))
      (node (ref "R18") (pin "2") (pinfunction "2_2") (pintype "passive"))
    )
    (net (code "54") (name "Net-(D14-A)") (class "Default")
      (node (ref "D14") (pin "2") (pinfunction "A_2") (pintype "passive"))
      (node (ref "R19") (pin "2") (pinfunction "2_2") (pintype "passive"))
    )
    (net (code "55") (name "Net-(D15-A)") (class "Default")
      (node (ref "D15") (pin "2") (pinfunction "A_2") (pintype "passive"))
      (node (ref "R20") (pin "2") (pinfunction "2_2") (pintype "passive"))
    )
    (net (code "56") (name "Net-(D16-A)") (class "Default")
      (node (ref "D16") (pin "2") (pinfunction "A_2") (pintype "passive"))
      (node (ref "R21") (pin "2") (pinfunction "2_2") (pintype "passive"))
    )
    (net (code "57") (name "Net-(U2-VCAP_1)") (class "Default")
      (node (ref "C21") (pin "1") (pinfunction "1_1") (pintype "passive"))
      (node (ref "U2") (pin "22") (pinfunction "VCAP_1_22") (pintype "passive"))
    )
    (net (code "58") (name "Net-(U2-VCAP_2)") (class "Default")
      (node (ref "C11") (pin "1") (pinfunction "1_1") (pintype "passive"))
      (node (ref "U2") (pin "46") (pinfunction "VCAP_2_46") (pintype "passive"))
    )
    (net (code "59") (name "Net-(USB_C-CC1)") (class "Default")
      (node (ref "R3") (pin "1") (pinfunction "1_1") (pintype "passive"))
      (node (ref "USB_C") (pin "A5") (pinfunction "CC1_A5") (pintype "passive"))
    )
    (net (code "60") (name "Net-(USB_C-CC2)") (class "Default")
      (node (ref "R4") (pin "1") (pinfunction "1_1") (pintype "passive"))
      (node (ref "USB_C") (pin "B5") (pinfunction "CC2_B5") (pintype "passive"))
    )
    (net (code "61") (name "unconnected-(STLinkV3-Pad8)") (class "Default")
      (node (ref "STLinkV3") (pin "8") (pinfunction "8_8") (pintype "passive+no_connect"))
    )
    (net (code "62") (name "unconnected-(STLinkV3-Pad9)") (class "Default")
      (node (ref "STLinkV3") (pin "9") (pinfunction "9_9") (pintype "passive+no_connect"))
    )
    (net (code "63") (name "unconnected-(STLinkV3-Pad11)") (class "Default")
      (node (ref "STLinkV3") (pin "11") (pinfunction "11_11") (pintype "passive+no_connect"))
    )
    (net (code "64") (name "unconnected-(STLinkV3-Pad12)") (class "Default")
      (node (ref "STLinkV3") (pin "12") (pinfunction "12_12") (pintype "passive+no_connect"))
    )
    (net (code "65") (name "unconnected-(STLinkV3-Pad13)") (class "Default")
      (node (ref "STLinkV3") (pin "13") (pinfunction "13_13") (pintype "passive+no_connect"))
    )
    (net (code "66") (name "unconnected-(STLinkV3-Pad14)") (class "Default")
      (node (ref "STLinkV3") (pin "14") (pinfunction "14_14") (pintype "passive+no_connect"))
    )
    (net (code "67") (name "unconnected-(U2-PB8-Pad45)") (class "Default")
      (node (ref "U2") (pin "45") (pinfunction "PB8_45") (pintype "passive"))
    )
    (net (code "68") (name "unconnected-(USB_C-RXN1-PadB10)") (class "Default")
      (node (ref "USB_C") (pin "B10") (pinfunction "RXN1_B10") (pintype "passive"))
    )
    (net (code "69") (name "unconnected-(USB_C-RXN2-PadA10)") (class "Default")
      (node (ref "USB_C") (pin "A10") (pinfunction "RXN2_A10") (pintype "passive"))
    )
    (net (code "70") (name "unconnected-(USB_C-RXP1-PadB11)") (class "Default")
      (node (ref "USB_C") (pin "B11") (pinfunction "RXP1_B11") (pintype "passive"))
    )
    (net (code "71") (name "unconnected-(USB_C-RXP2-PadA11)") (class "Default")
      (node (ref "USB_C") (pin "A11") (pinfunction "RXP2_A11") (pintype "passive"))
    )
    (net (code "72") (name "unconnected-(USB_C-SBU1-PadA8)") (class "Default")
      (node (ref "USB_C") (pin "A8") (pinfunction "SBU1_A8") (pintype "passive"))
    )
    (net (code "73") (name "unconnected-(USB_C-SBU2-PadB8)") (class "Default")
      (node (ref "USB_C") (pin "B8") (pinfunction "SBU2_B8") (pintype "passive"))
    )
    (net (code "74") (name "unconnected-(USB_C-TXN1-PadA3)") (class "Default")
      (node (ref "USB_C") (pin "A3") (pinfunction "TXN1_A3") (pintype "passive"))
    )
    (net (code "75") (name "unconnected-(USB_C-TXN2-PadB3)") (class "Default")
      (node (ref "USB_C") (pin "B3") (pinfunction "TXN2_B3") (pintype "passive"))
    )
    (net (code "76") (name "unconnected-(USB_C-TXP1-PadA2)") (class "Default")
      (node (ref "USB_C") (pin "A2") (pinfunction "TXP1_A2") (pintype "passive"))
    )
    (net (code "77") (name "unconnected-(USB_C-TXP2-PadB2)") (class "Default")
      (node (ref "USB_C") (pin "B2") (pinfunction "TXP2_B2") (pintype "passive"))
    )
    (net (code "78") (name "unconnected-(Y2-NC-Pad4)") (class "Default")
      (node (ref "Y2") (pin "4") (pinfunction "NC_4") (pintype "passive+no_connect"))
    )
  )
)
